# TEMPERATURE_MEASUREMENT.net
KiCad netlist of a schematic drawn in Altium Designer
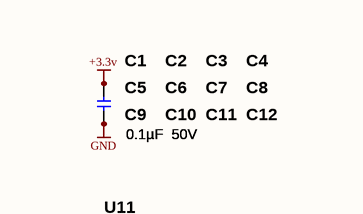
[diagram p0: TEMPERATURE_MEASUREMENT.SchDoc, top left]
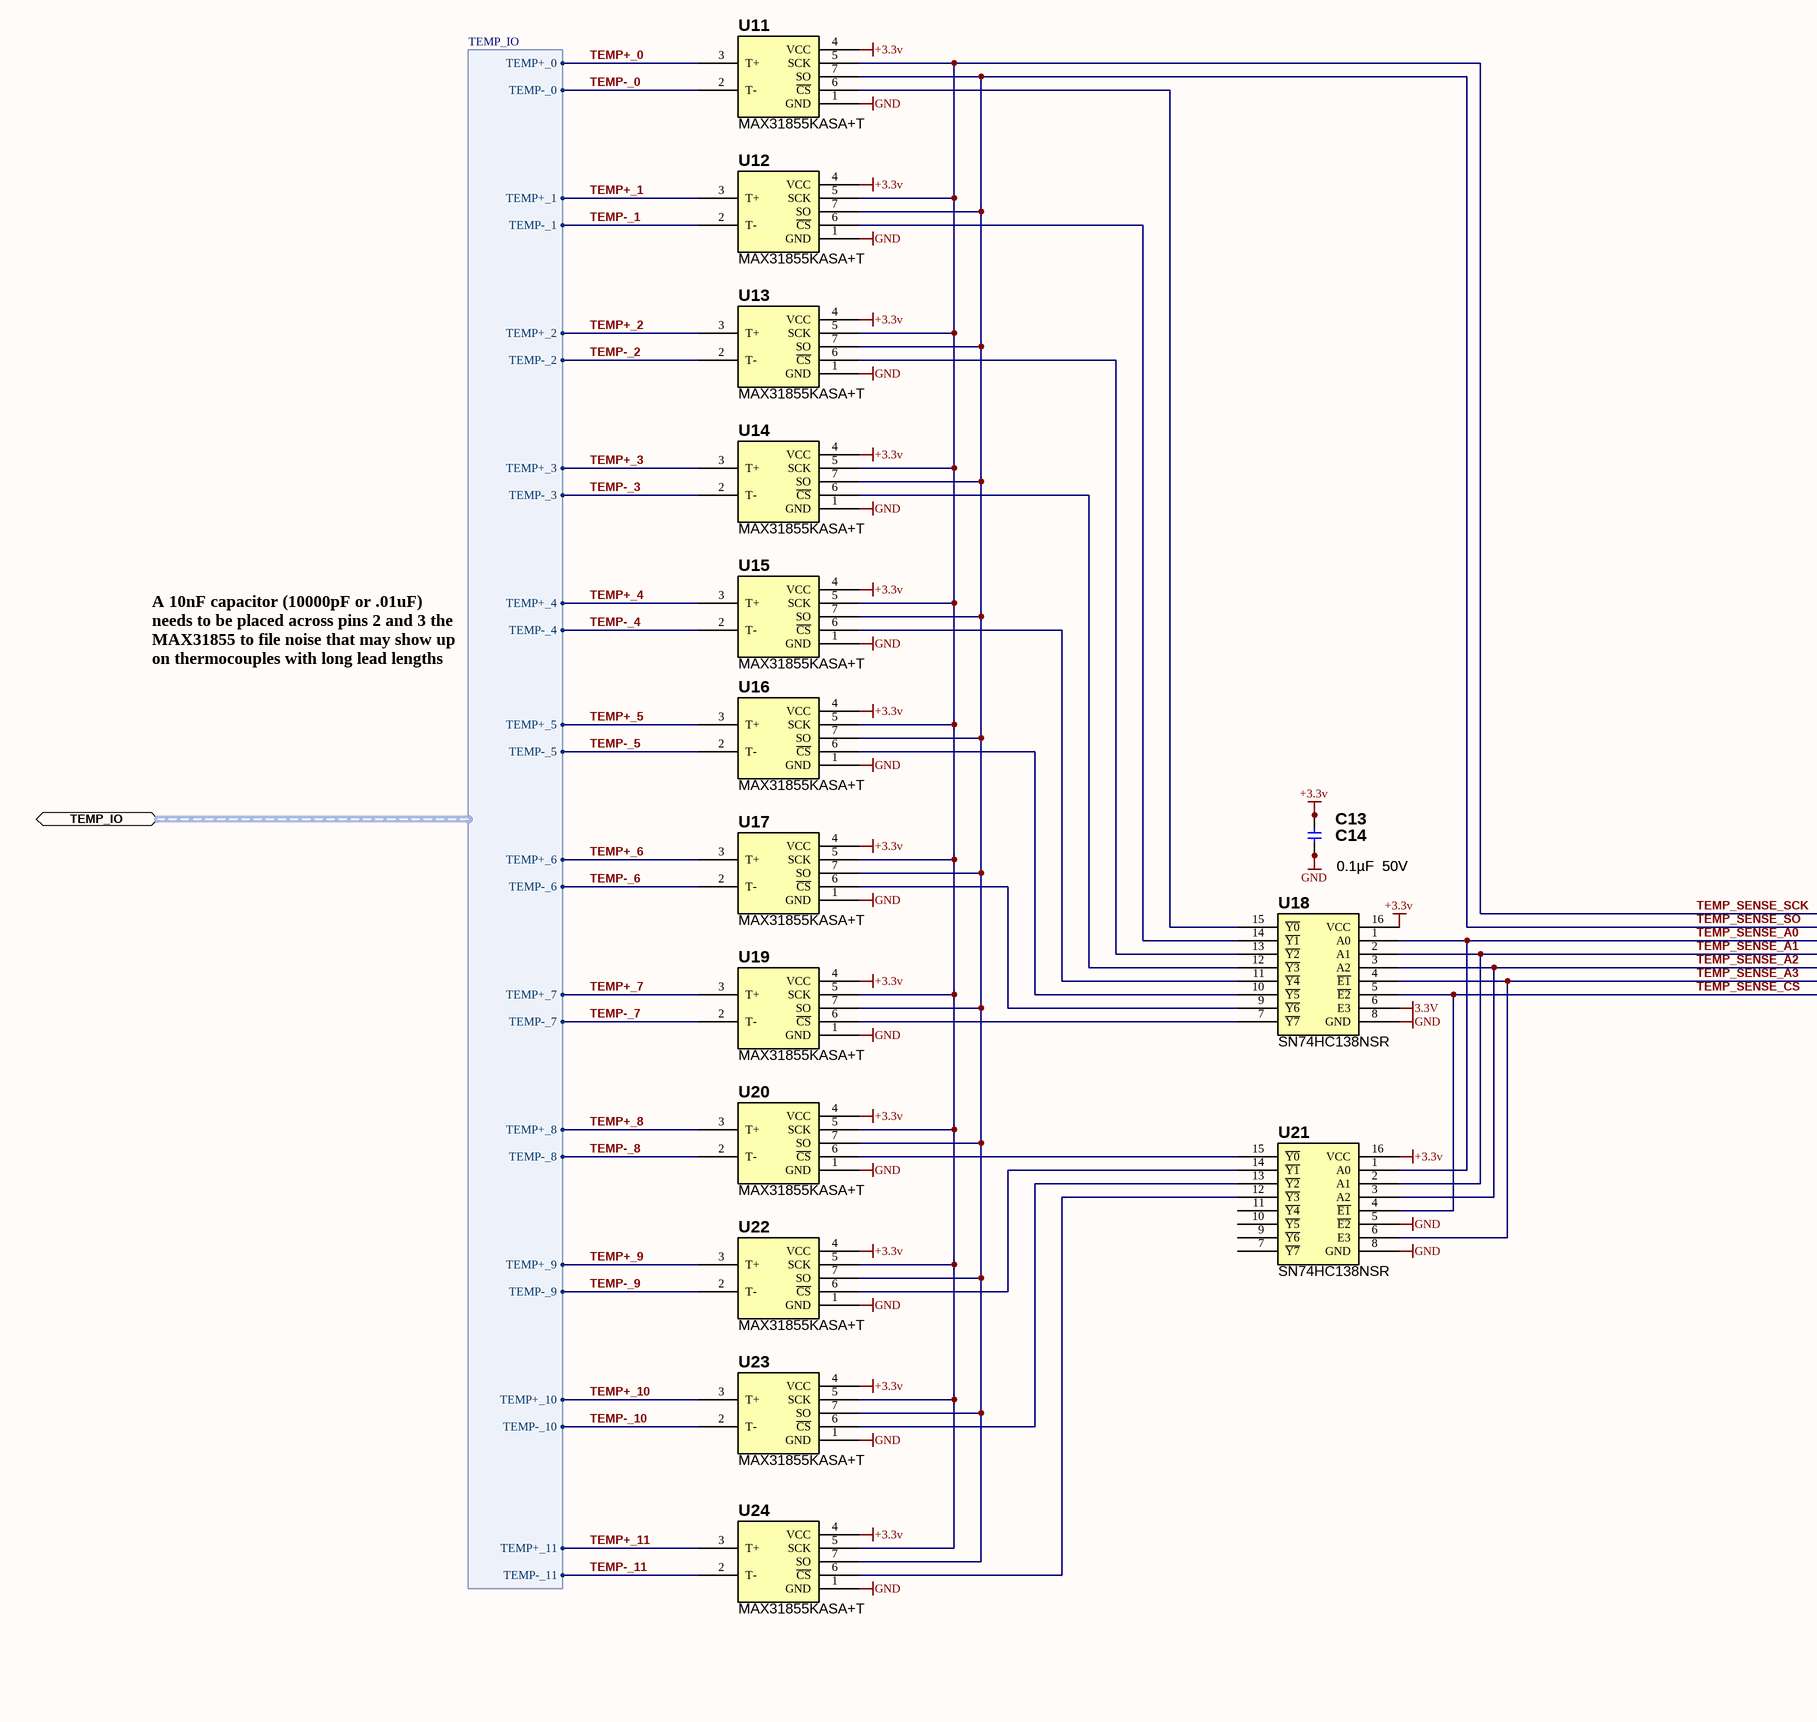
[diagram p1: TEMPERATURE_MEASUREMENT.SchDoc, bottom left]
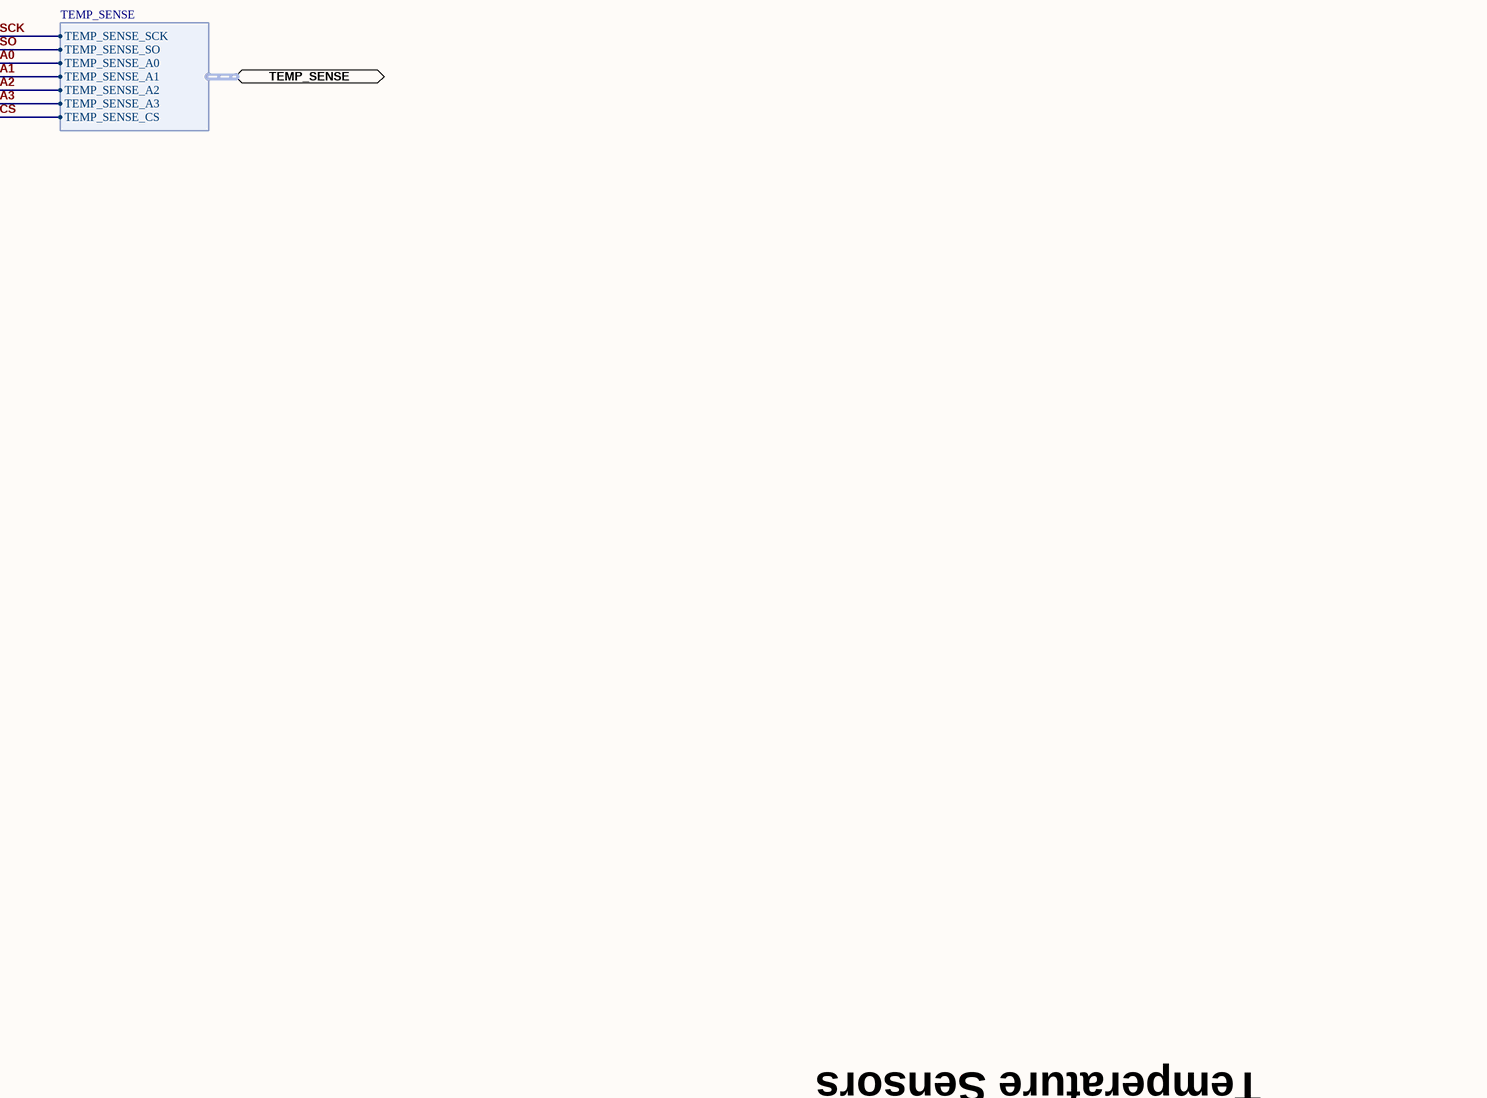
[diagram p2: TEMPERATURE_MEASUREMENT.SchDoc, bottom right]

(export (version "E")
  (design (tool "Eeschema 10.0.6"))
  (components
    (comp (ref "C1")
      (value "0.1µF  50V")
      (footprint "C0805_LD")
      (description "CAP CER 0.1UF 50V 10% X7R 0805")
      (fields
        (field (name "MANUFACTURER PART NUMBER") "GRM21BR71H104KA01L")
        (field (name "MANUFACTURER") "Murata Electronics North America")
      )
      (libsource (lib "Capacitors") (part "C_2P_NP"))
    )
    (comp (ref "C2")
      (value "0.1µF  50V")
      (footprint "C0805_LD")
      (description "CAP CER 0.1UF 50V 10% X7R 0805")
      (fields
        (field (name "MANUFACTURER PART NUMBER") "GRM21BR71H104KA01L")
        (field (name "MANUFACTURER") "Murata Electronics North America")
      )
      (libsource (lib "Capacitors") (part "C_2P_NP"))
    )
    (comp (ref "C3")
      (value "0.1µF  50V")
      (footprint "C0805_LD")
      (description "CAP CER 0.1UF 50V 10% X7R 0805")
      (fields
        (field (name "MANUFACTURER PART NUMBER") "GRM21BR71H104KA01L")
        (field (name "MANUFACTURER") "Murata Electronics North America")
      )
      (libsource (lib "Capacitors") (part "C_2P_NP"))
    )
    (comp (ref "C4")
      (value "0.1µF  50V")
      (footprint "C0805_LD")
      (description "CAP CER 0.1UF 50V 10% X7R 0805")
      (fields
        (field (name "MANUFACTURER PART NUMBER") "GRM21BR71H104KA01L")
        (field (name "MANUFACTURER") "Murata Electronics North America")
      )
      (libsource (lib "Capacitors") (part "C_2P_NP"))
    )
    (comp (ref "C5")
      (value "0.1µF  50V")
      (footprint "C0805_LD")
      (description "CAP CER 0.1UF 50V 10% X7R 0805")
      (fields
        (field (name "MANUFACTURER PART NUMBER") "GRM21BR71H104KA01L")
        (field (name "MANUFACTURER") "Murata Electronics North America")
      )
      (libsource (lib "Capacitors") (part "C_2P_NP"))
    )
    (comp (ref "C6")
      (value "0.1µF  50V")
      (footprint "C0805_LD")
      (description "CAP CER 0.1UF 50V 10% X7R 0805")
      (fields
        (field (name "MANUFACTURER PART NUMBER") "GRM21BR71H104KA01L")
        (field (name "MANUFACTURER") "Murata Electronics North America")
      )
      (libsource (lib "Capacitors") (part "C_2P_NP"))
    )
    (comp (ref "C7")
      (value "0.1µF  50V")
      (footprint "C0805_LD")
      (description "CAP CER 0.1UF 50V 10% X7R 0805")
      (fields
        (field (name "MANUFACTURER PART NUMBER") "GRM21BR71H104KA01L")
        (field (name "MANUFACTURER") "Murata Electronics North America")
      )
      (libsource (lib "Capacitors") (part "C_2P_NP"))
    )
    (comp (ref "C8")
      (value "0.1µF  50V")
      (footprint "C0805_LD")
      (description "CAP CER 0.1UF 50V 10% X7R 0805")
      (fields
        (field (name "MANUFACTURER PART NUMBER") "GRM21BR71H104KA01L")
        (field (name "MANUFACTURER") "Murata Electronics North America")
      )
      (libsource (lib "Capacitors") (part "C_2P_NP"))
    )
    (comp (ref "C9")
      (value "0.1µF  50V")
      (footprint "C0805_LD")
      (description "CAP CER 0.1UF 50V 10% X7R 0805")
      (fields
        (field (name "MANUFACTURER PART NUMBER") "GRM21BR71H104KA01L")
        (field (name "MANUFACTURER") "Murata Electronics North America")
      )
      (libsource (lib "Capacitors") (part "C_2P_NP"))
    )
    (comp (ref "C10")
      (value "0.1µF  50V")
      (footprint "C0805_LD")
      (description "CAP CER 0.1UF 50V 10% X7R 0805")
      (fields
        (field (name "MANUFACTURER PART NUMBER") "GRM21BR71H104KA01L")
        (field (name "MANUFACTURER") "Murata Electronics North America")
      )
      (libsource (lib "Capacitors") (part "C_2P_NP"))
    )
    (comp (ref "C11")
      (value "0.1µF  50V")
      (footprint "C0805_LD")
      (description "CAP CER 0.1UF 50V 10% X7R 0805")
      (fields
        (field (name "MANUFACTURER PART NUMBER") "GRM21BR71H104KA01L")
        (field (name "MANUFACTURER") "Murata Electronics North America")
      )
      (libsource (lib "Capacitors") (part "C_2P_NP"))
    )
    (comp (ref "C12")
      (value "0.1µF  50V")
      (footprint "C0805_LD")
      (description "CAP CER 0.1UF 50V 10% X7R 0805")
      (fields
        (field (name "MANUFACTURER PART NUMBER") "GRM21BR71H104KA01L")
        (field (name "MANUFACTURER") "Murata Electronics North America")
      )
      (libsource (lib "Capacitors") (part "C_2P_NP"))
    )
    (comp (ref "C13")
      (value "0.1µF  50V")
      (footprint "C0805_LD")
      (description "CAP CER 0.1UF 50V 10% X7R 0805")
      (fields
        (field (name "MANUFACTURER PART NUMBER") "GRM21BR71H104KA01L")
        (field (name "MANUFACTURER") "Murata Electronics North America")
      )
      (libsource (lib "Capacitors") (part "C_2P_NP"))
    )
    (comp (ref "C14")
      (value "0.1µF  50V")
      (footprint "C0805_LD")
      (description "CAP CER 0.1UF 50V 10% X7R 0805")
      (fields
        (field (name "MANUFACTURER PART NUMBER") "GRM21BR71H104KA01L")
        (field (name "MANUFACTURER") "Murata Electronics North America")
      )
      (libsource (lib "Capacitors") (part "C_2P_NP"))
    )
    (comp (ref "U11")
      (value "MAX31855KASA+T")
      (footprint "SOIC 8")
      (description "IC CONV THERMOCOUPLE-DGTL 8SOIC")
      (fields (field (name "MANUFACTURER") "Maxim Integrated"))
      (libsource (lib "eIC") (part "MAX31855KASA+T"))
    )
    (comp (ref "U12")
      (value "MAX31855KASA+T")
      (footprint "SOIC 8")
      (description "IC CONV THERMOCOUPLE-DGTL 8SOIC")
      (fields (field (name "MANUFACTURER") "Maxim Integrated"))
      (libsource (lib "eIC") (part "MAX31855KASA+T"))
    )
    (comp (ref "U13")
      (value "MAX31855KASA+T")
      (footprint "SOIC 8")
      (description "IC CONV THERMOCOUPLE-DGTL 8SOIC")
      (fields (field (name "MANUFACTURER") "Maxim Integrated"))
      (libsource (lib "eIC") (part "MAX31855KASA+T"))
    )
    (comp (ref "U14")
      (value "MAX31855KASA+T")
      (footprint "SOIC 8")
      (description "IC CONV THERMOCOUPLE-DGTL 8SOIC")
      (fields (field (name "MANUFACTURER") "Maxim Integrated"))
      (libsource (lib "eIC") (part "MAX31855KASA+T"))
    )
    (comp (ref "U15")
      (value "MAX31855KASA+T")
      (footprint "SOIC 8")
      (description "IC CONV THERMOCOUPLE-DGTL 8SOIC")
      (fields (field (name "MANUFACTURER") "Maxim Integrated"))
      (libsource (lib "eIC") (part "MAX31855KASA+T"))
    )
    (comp (ref "U16")
      (value "MAX31855KASA+T")
      (footprint "SOIC 8")
      (description "IC CONV THERMOCOUPLE-DGTL 8SOIC")
      (fields (field (name "MANUFACTURER") "Maxim Integrated"))
      (libsource (lib "eIC") (part "MAX31855KASA+T"))
    )
    (comp (ref "U17")
      (value "MAX31855KASA+T")
      (footprint "SOIC 8")
      (description "IC CONV THERMOCOUPLE-DGTL 8SOIC")
      (fields (field (name "MANUFACTURER") "Maxim Integrated"))
      (libsource (lib "eIC") (part "MAX31855KASA+T"))
    )
    (comp (ref "U18")
      (value "SN74HC138NSR")
      (footprint "SOIC 16 Wide")
      (description "IC DECODER/DEMUX 3-8 LINE 16SO")
      (fields (field (name "MANUFACTURER") "Texas Instruments"))
      (libsource (lib "eIC") (part "SN74HC138NSR"))
    )
    (comp (ref "U19")
      (value "MAX31855KASA+T")
      (footprint "SOIC 8")
      (description "IC CONV THERMOCOUPLE-DGTL 8SOIC")
      (fields (field (name "MANUFACTURER") "Maxim Integrated"))
      (libsource (lib "eIC") (part "MAX31855KASA+T"))
    )
    (comp (ref "U20")
      (value "MAX31855KASA+T")
      (footprint "SOIC 8")
      (description "IC CONV THERMOCOUPLE-DGTL 8SOIC")
      (fields (field (name "MANUFACTURER") "Maxim Integrated"))
      (libsource (lib "eIC") (part "MAX31855KASA+T"))
    )
    (comp (ref "U21")
      (value "SN74HC138NSR")
      (footprint "SOIC 16 Wide")
      (description "IC DECODER/DEMUX 3-8 LINE 16SO")
      (fields (field (name "MANUFACTURER") "Texas Instruments"))
      (libsource (lib "eIC") (part "SN74HC138NSR"))
    )
    (comp (ref "U22")
      (value "MAX31855KASA+T")
      (footprint "SOIC 8")
      (description "IC CONV THERMOCOUPLE-DGTL 8SOIC")
      (fields (field (name "MANUFACTURER") "Maxim Integrated"))
      (libsource (lib "eIC") (part "MAX31855KASA+T"))
    )
    (comp (ref "U23")
      (value "MAX31855KASA+T")
      (footprint "SOIC 8")
      (description "IC CONV THERMOCOUPLE-DGTL 8SOIC")
      (fields (field (name "MANUFACTURER") "Maxim Integrated"))
      (libsource (lib "eIC") (part "MAX31855KASA+T"))
    )
    (comp (ref "U24")
      (value "MAX31855KASA+T")
      (footprint "SOIC 8")
      (description "IC CONV THERMOCOUPLE-DGTL 8SOIC")
      (fields (field (name "MANUFACTURER") "Maxim Integrated"))
      (libsource (lib "eIC") (part "MAX31855KASA+T"))
    )
  )
  (nets
    (net (code "3") (name "+3.3v") (class "Default")
      (node (ref "C1") (pin "2") (pinfunction "2_2") (pintype "passive"))
      (node (ref "C10") (pin "2") (pinfunction "2_2") (pintype "passive"))
      (node (ref "C11") (pin "2") (pinfunction "2_2") (pintype "passive"))
      (node (ref "C12") (pin "2") (pinfunction "2_2") (pintype "passive"))
      (node (ref "C13") (pin "2") (pinfunction "2_2") (pintype "passive"))
      (node (ref "C14") (pin "2") (pinfunction "2_2") (pintype "passive"))
      (node (ref "C2") (pin "2") (pinfunction "2_2") (pintype "passive"))
      (node (ref "C3") (pin "2") (pinfunction "2_2") (pintype "passive"))
      (node (ref "C4") (pin "2") (pinfunction "2_2") (pintype "passive"))
      (node (ref "C5") (pin "2") (pinfunction "2_2") (pintype "passive"))
      (node (ref "C6") (pin "2") (pinfunction "2_2") (pintype "passive"))
      (node (ref "C7") (pin "2") (pinfunction "2_2") (pintype "passive"))
      (node (ref "C8") (pin "2") (pinfunction "2_2") (pintype "passive"))
      (node (ref "C9") (pin "2") (pinfunction "2_2") (pintype "passive"))
      (node (ref "U11") (pin "4") (pinfunction "VCC_4") (pintype "passive"))
      (node (ref "U12") (pin "4") (pinfunction "VCC_4") (pintype "passive"))
      (node (ref "U13") (pin "4") (pinfunction "VCC_4") (pintype "passive"))
      (node (ref "U14") (pin "4") (pinfunction "VCC_4") (pintype "passive"))
      (node (ref "U15") (pin "4") (pinfunction "VCC_4") (pintype "passive"))
      (node (ref "U16") (pin "4") (pinfunction "VCC_4") (pintype "passive"))
      (node (ref "U17") (pin "4") (pinfunction "VCC_4") (pintype "passive"))
      (node (ref "U18") (pin "16") (pinfunction "VCC_16") (pintype "passive"))
      (node (ref "U19") (pin "4") (pinfunction "VCC_4") (pintype "passive"))
      (node (ref "U20") (pin "4") (pinfunction "VCC_4") (pintype "passive"))
      (node (ref "U21") (pin "16") (pinfunction "VCC_16") (pintype "passive"))
      (node (ref "U22") (pin "4") (pinfunction "VCC_4") (pintype "passive"))
      (node (ref "U23") (pin "4") (pinfunction "VCC_4") (pintype "passive"))
      (node (ref "U24") (pin "4") (pinfunction "VCC_4") (pintype "passive"))
    )
    (net (code "4") (name "/TEMP+_0") (class "Default")
      (node (ref "U11") (pin "3") (pinfunction "T+_3") (pintype "passive"))
    )
    (net (code "5") (name "/TEMP+_1") (class "Default")
      (node (ref "U12") (pin "3") (pinfunction "T+_3") (pintype "passive"))
    )
    (net (code "6") (name "/TEMP+_2") (class "Default")
      (node (ref "U13") (pin "3") (pinfunction "T+_3") (pintype "passive"))
    )
    (net (code "7") (name "/TEMP+_3") (class "Default")
      (node (ref "U14") (pin "3") (pinfunction "T+_3") (pintype "passive"))
    )
    (net (code "8") (name "/TEMP+_4") (class "Default")
      (node (ref "U15") (pin "3") (pinfunction "T+_3") (pintype "passive"))
    )
    (net (code "9") (name "/TEMP+_5") (class "Default")
      (node (ref "U16") (pin "3") (pinfunction "T+_3") (pintype "passive"))
    )
    (net (code "10") (name "/TEMP+_6") (class "Default")
      (node (ref "U17") (pin "3") (pinfunction "T+_3") (pintype "passive"))
    )
    (net (code "11") (name "/TEMP+_7") (class "Default")
      (node (ref "U19") (pin "3") (pinfunction "T+_3") (pintype "passive"))
    )
    (net (code "12") (name "/TEMP+_8") (class "Default")
      (node (ref "U20") (pin "3") (pinfunction "T+_3") (pintype "passive"))
    )
    (net (code "13") (name "/TEMP+_9") (class "Default")
      (node (ref "U22") (pin "3") (pinfunction "T+_3") (pintype "passive"))
    )
    (net (code "14") (name "/TEMP+_10") (class "Default")
      (node (ref "U23") (pin "3") (pinfunction "T+_3") (pintype "passive"))
    )
    (net (code "15") (name "/TEMP+_11") (class "Default")
      (node (ref "U24") (pin "3") (pinfunction "T+_3") (pintype "passive"))
    )
    (net (code "16") (name "/TEMP-_0") (class "Default")
      (node (ref "U11") (pin "2") (pinfunction "T-_2") (pintype "passive"))
    )
    (net (code "17") (name "/TEMP-_1") (class "Default")
      (node (ref "U12") (pin "2") (pinfunction "T-_2") (pintype "passive"))
    )
    (net (code "18") (name "/TEMP-_2") (class "Default")
      (node (ref "U13") (pin "2") (pinfunction "T-_2") (pintype "passive"))
    )
    (net (code "19") (name "/TEMP-_3") (class "Default")
      (node (ref "U14") (pin "2") (pinfunction "T-_2") (pintype "passive"))
    )
    (net (code "20") (name "/TEMP-_4") (class "Default")
      (node (ref "U15") (pin "2") (pinfunction "T-_2") (pintype "passive"))
    )
    (net (code "21") (name "/TEMP-_5") (class "Default")
      (node (ref "U16") (pin "2") (pinfunction "T-_2") (pintype "passive"))
    )
    (net (code "22") (name "/TEMP-_6") (class "Default")
      (node (ref "U17") (pin "2") (pinfunction "T-_2") (pintype "passive"))
    )
    (net (code "23") (name "/TEMP-_7") (class "Default")
      (node (ref "U19") (pin "2") (pinfunction "T-_2") (pintype "passive"))
    )
    (net (code "24") (name "/TEMP-_8") (class "Default")
      (node (ref "U20") (pin "2") (pinfunction "T-_2") (pintype "passive"))
    )
    (net (code "25") (name "/TEMP-_9") (class "Default")
      (node (ref "U22") (pin "2") (pinfunction "T-_2") (pintype "passive"))
    )
    (net (code "26") (name "/TEMP-_10") (class "Default")
      (node (ref "U23") (pin "2") (pinfunction "T-_2") (pintype "passive"))
    )
    (net (code "27") (name "/TEMP-_11") (class "Default")
      (node (ref "U24") (pin "2") (pinfunction "T-_2") (pintype "passive"))
    )
    (net (code "28") (name "/TEMP_SENSE_A0") (class "Default")
      (node (ref "U18") (pin "1") (pinfunction "A0_1") (pintype "passive"))
      (node (ref "U21") (pin "1") (pinfunction "A0_1") (pintype "passive"))
    )
    (net (code "29") (name "/TEMP_SENSE_A1") (class "Default")
      (node (ref "U18") (pin "2") (pinfunction "A1_2") (pintype "passive"))
      (node (ref "U21") (pin "2") (pinfunction "A1_2") (pintype "passive"))
    )
    (net (code "30") (name "/TEMP_SENSE_A2") (class "Default")
      (node (ref "U18") (pin "3") (pinfunction "A2_3") (pintype "passive"))
      (node (ref "U21") (pin "3") (pinfunction "A2_3") (pintype "passive"))
    )
    (net (code "31") (name "/TEMP_SENSE_A3") (class "Default")
      (node (ref "U18") (pin "4") (pinfunction "~{E1}_4") (pintype "passive"))
      (node (ref "U21") (pin "6") (pinfunction "E3_6") (pintype "passive"))
    )
    (net (code "32") (name "/TEMP_SENSE_CS") (class "Default")
      (node (ref "U18") (pin "5") (pinfunction "~{E2}_5") (pintype "passive"))
      (node (ref "U21") (pin "4") (pinfunction "~{E1}_4") (pintype "passive"))
    )
    (net (code "33") (name "/TEMP_SENSE_SCK") (class "Default")
      (node (ref "U11") (pin "5") (pinfunction "SCK_5") (pintype "passive"))
      (node (ref "U12") (pin "5") (pinfunction "SCK_5") (pintype "passive"))
      (node (ref "U13") (pin "5") (pinfunction "SCK_5") (pintype "passive"))
      (node (ref "U14") (pin "5") (pinfunction "SCK_5") (pintype "passive"))
      (node (ref "U15") (pin "5") (pinfunction "SCK_5") (pintype "passive"))
      (node (ref "U16") (pin "5") (pinfunction "SCK_5") (pintype "passive"))
      (node (ref "U17") (pin "5") (pinfunction "SCK_5") (pintype "passive"))
      (node (ref "U19") (pin "5") (pinfunction "SCK_5") (pintype "passive"))
      (node (ref "U20") (pin "5") (pinfunction "SCK_5") (pintype "passive"))
      (node (ref "U22") (pin "5") (pinfunction "SCK_5") (pintype "passive"))
      (node (ref "U23") (pin "5") (pinfunction "SCK_5") (pintype "passive"))
      (node (ref "U24") (pin "5") (pinfunction "SCK_5") (pintype "passive"))
    )
    (net (code "34") (name "/TEMP_SENSE_SO") (class "Default")
      (node (ref "U11") (pin "7") (pinfunction "SO_7") (pintype "passive"))
      (node (ref "U12") (pin "7") (pinfunction "SO_7") (pintype "passive"))
      (node (ref "U13") (pin "7") (pinfunction "SO_7") (pintype "passive"))
      (node (ref "U14") (pin "7") (pinfunction "SO_7") (pintype "passive"))
      (node (ref "U15") (pin "7") (pinfunction "SO_7") (pintype "passive"))
      (node (ref "U16") (pin "7") (pinfunction "SO_7") (pintype "passive"))
      (node (ref "U17") (pin "7") (pinfunction "SO_7") (pintype "passive"))
      (node (ref "U19") (pin "7") (pinfunction "SO_7") (pintype "passive"))
      (node (ref "U20") (pin "7") (pinfunction "SO_7") (pintype "passive"))
      (node (ref "U22") (pin "7") (pinfunction "SO_7") (pintype "passive"))
      (node (ref "U23") (pin "7") (pinfunction "SO_7") (pintype "passive"))
      (node (ref "U24") (pin "7") (pinfunction "SO_7") (pintype "passive"))
    )
    (net (code "37") (name "3.3V") (class "Default")
      (node (ref "U18") (pin "6") (pinfunction "E3_6") (pintype "passive"))
    )
    (net (code "38") (name "GND") (class "Default")
      (node (ref "C1") (pin "1") (pinfunction "1_1") (pintype "passive"))
      (node (ref "C10") (pin "1") (pinfunction "1_1") (pintype "passive"))
      (node (ref "C11") (pin "1") (pinfunction "1_1") (pintype "passive"))
      (node (ref "C12") (pin "1") (pinfunction "1_1") (pintype "passive"))
      (node (ref "C13") (pin "1") (pinfunction "1_1") (pintype "passive"))
      (node (ref "C14") (pin "1") (pinfunction "1_1") (pintype "passive"))
      (node (ref "C2") (pin "1") (pinfunction "1_1") (pintype "passive"))
      (node (ref "C3") (pin "1") (pinfunction "1_1") (pintype "passive"))
      (node (ref "C4") (pin "1") (pinfunction "1_1") (pintype "passive"))
      (node (ref "C5") (pin "1") (pinfunction "1_1") (pintype "passive"))
      (node (ref "C6") (pin "1") (pinfunction "1_1") (pintype "passive"))
      (node (ref "C7") (pin "1") (pinfunction "1_1") (pintype "passive"))
      (node (ref "C8") (pin "1") (pinfunction "1_1") (pintype "passive"))
      (node (ref "C9") (pin "1") (pinfunction "1_1") (pintype "passive"))
      (node (ref "U11") (pin "1") (pinfunction "GND_1") (pintype "passive"))
      (node (ref "U12") (pin "1") (pinfunction "GND_1") (pintype "passive"))
      (node (ref "U13") (pin "1") (pinfunction "GND_1") (pintype "passive"))
      (node (ref "U14") (pin "1") (pinfunction "GND_1") (pintype "passive"))
      (node (ref "U15") (pin "1") (pinfunction "GND_1") (pintype "passive"))
      (node (ref "U16") (pin "1") (pinfunction "GND_1") (pintype "passive"))
      (node (ref "U17") (pin "1") (pinfunction "GND_1") (pintype "passive"))
      (node (ref "U18") (pin "8") (pinfunction "GND_8") (pintype "passive"))
      (node (ref "U19") (pin "1") (pinfunction "GND_1") (pintype "passive"))
      (node (ref "U20") (pin "1") (pinfunction "GND_1") (pintype "passive"))
      (node (ref "U21") (pin "5") (pinfunction "~{E2}_5") (pintype "passive"))
      (node (ref "U21") (pin "8") (pinfunction "GND_8") (pintype "passive"))
      (node (ref "U22") (pin "1") (pinfunction "GND_1") (pintype "passive"))
      (node (ref "U23") (pin "1") (pinfunction "GND_1") (pintype "passive"))
      (node (ref "U24") (pin "1") (pinfunction "GND_1") (pintype "passive"))
    )
    (net (code "39") (name "Net-(U11-~{CS})") (class "Default")
      (node (ref "U11") (pin "6") (pinfunction "~{CS}_6") (pintype "passive"))
      (node (ref "U18") (pin "15") (pinfunction "~{Y0}_15") (pintype "passive"))
    )
    (net (code "40") (name "Net-(U12-~{CS})") (class "Default")
      (node (ref "U12") (pin "6") (pinfunction "~{CS}_6") (pintype "passive"))
      (node (ref "U18") (pin "14") (pinfunction "~{Y1}_14") (pintype "passive"))
    )
    (net (code "41") (name "Net-(U13-~{CS})") (class "Default")
      (node (ref "U13") (pin "6") (pinfunction "~{CS}_6") (pintype "passive"))
      (node (ref "U18") (pin "13") (pinfunction "~{Y2}_13") (pintype "passive"))
    )
    (net (code "42") (name "Net-(U14-~{CS})") (class "Default")
      (node (ref "U14") (pin "6") (pinfunction "~{CS}_6") (pintype "passive"))
      (node (ref "U18") (pin "12") (pinfunction "~{Y3}_12") (pintype "passive"))
    )
    (net (code "43") (name "Net-(U15-~{CS})") (class "Default")
      (node (ref "U15") (pin "6") (pinfunction "~{CS}_6") (pintype "passive"))
      (node (ref "U18") (pin "11") (pinfunction "~{Y4}_11") (pintype "passive"))
    )
    (net (code "44") (name "Net-(U16-~{CS})") (class "Default")
      (node (ref "U16") (pin "6") (pinfunction "~{CS}_6") (pintype "passive"))
      (node (ref "U18") (pin "10") (pinfunction "~{Y5}_10") (pintype "passive"))
    )
    (net (code "45") (name "Net-(U17-~{CS})") (class "Default")
      (node (ref "U17") (pin "6") (pinfunction "~{CS}_6") (pintype "passive"))
      (node (ref "U18") (pin "9") (pinfunction "~{Y6}_9") (pintype "passive"))
    )
    (net (code "46") (name "Net-(U18-~{Y7})") (class "Default")
      (node (ref "U18") (pin "7") (pinfunction "~{Y7}_7") (pintype "passive"))
      (node (ref "U19") (pin "6") (pinfunction "~{CS}_6") (pintype "passive"))
    )
    (net (code "47") (name "Net-(U20-~{CS})") (class "Default")
      (node (ref "U20") (pin "6") (pinfunction "~{CS}_6") (pintype "passive"))
      (node (ref "U21") (pin "15") (pinfunction "~{Y0}_15") (pintype "passive"))
    )
    (net (code "48") (name "Net-(U21-~{Y1})") (class "Default")
      (node (ref "U21") (pin "14") (pinfunction "~{Y1}_14") (pintype "passive"))
      (node (ref "U22") (pin "6") (pinfunction "~{CS}_6") (pintype "passive"))
    )
    (net (code "49") (name "Net-(U21-~{Y2})") (class "Default")
      (node (ref "U21") (pin "13") (pinfunction "~{Y2}_13") (pintype "passive"))
      (node (ref "U23") (pin "6") (pinfunction "~{CS}_6") (pintype "passive"))
    )
    (net (code "50") (name "Net-(U21-~{Y3})") (class "Default")
      (node (ref "U21") (pin "12") (pinfunction "~{Y3}_12") (pintype "passive"))
      (node (ref "U24") (pin "6") (pinfunction "~{CS}_6") (pintype "passive"))
    )
    (net (code "51") (name "unconnected-(U21-~{Y4}-Pad11)") (class "Default")
      (node (ref "U21") (pin "11") (pinfunction "~{Y4}_11") (pintype "passive"))
    )
    (net (code "52") (name "unconnected-(U21-~{Y5}-Pad10)") (class "Default")
      (node (ref "U21") (pin "10") (pinfunction "~{Y5}_10") (pintype "passive"))
    )
    (net (code "53") (name "unconnected-(U21-~{Y6}-Pad9)") (class "Default")
      (node (ref "U21") (pin "9") (pinfunction "~{Y6}_9") (pintype "passive"))
    )
    (net (code "54") (name "unconnected-(U21-~{Y7}-Pad7)") (class "Default")
      (node (ref "U21") (pin "7") (pinfunction "~{Y7}_7") (pintype "passive"))
    )
  )
)
